# TH_itsy_bitsy_reference_board.net
KiCad netlist of a schematic drawn in EAGLE
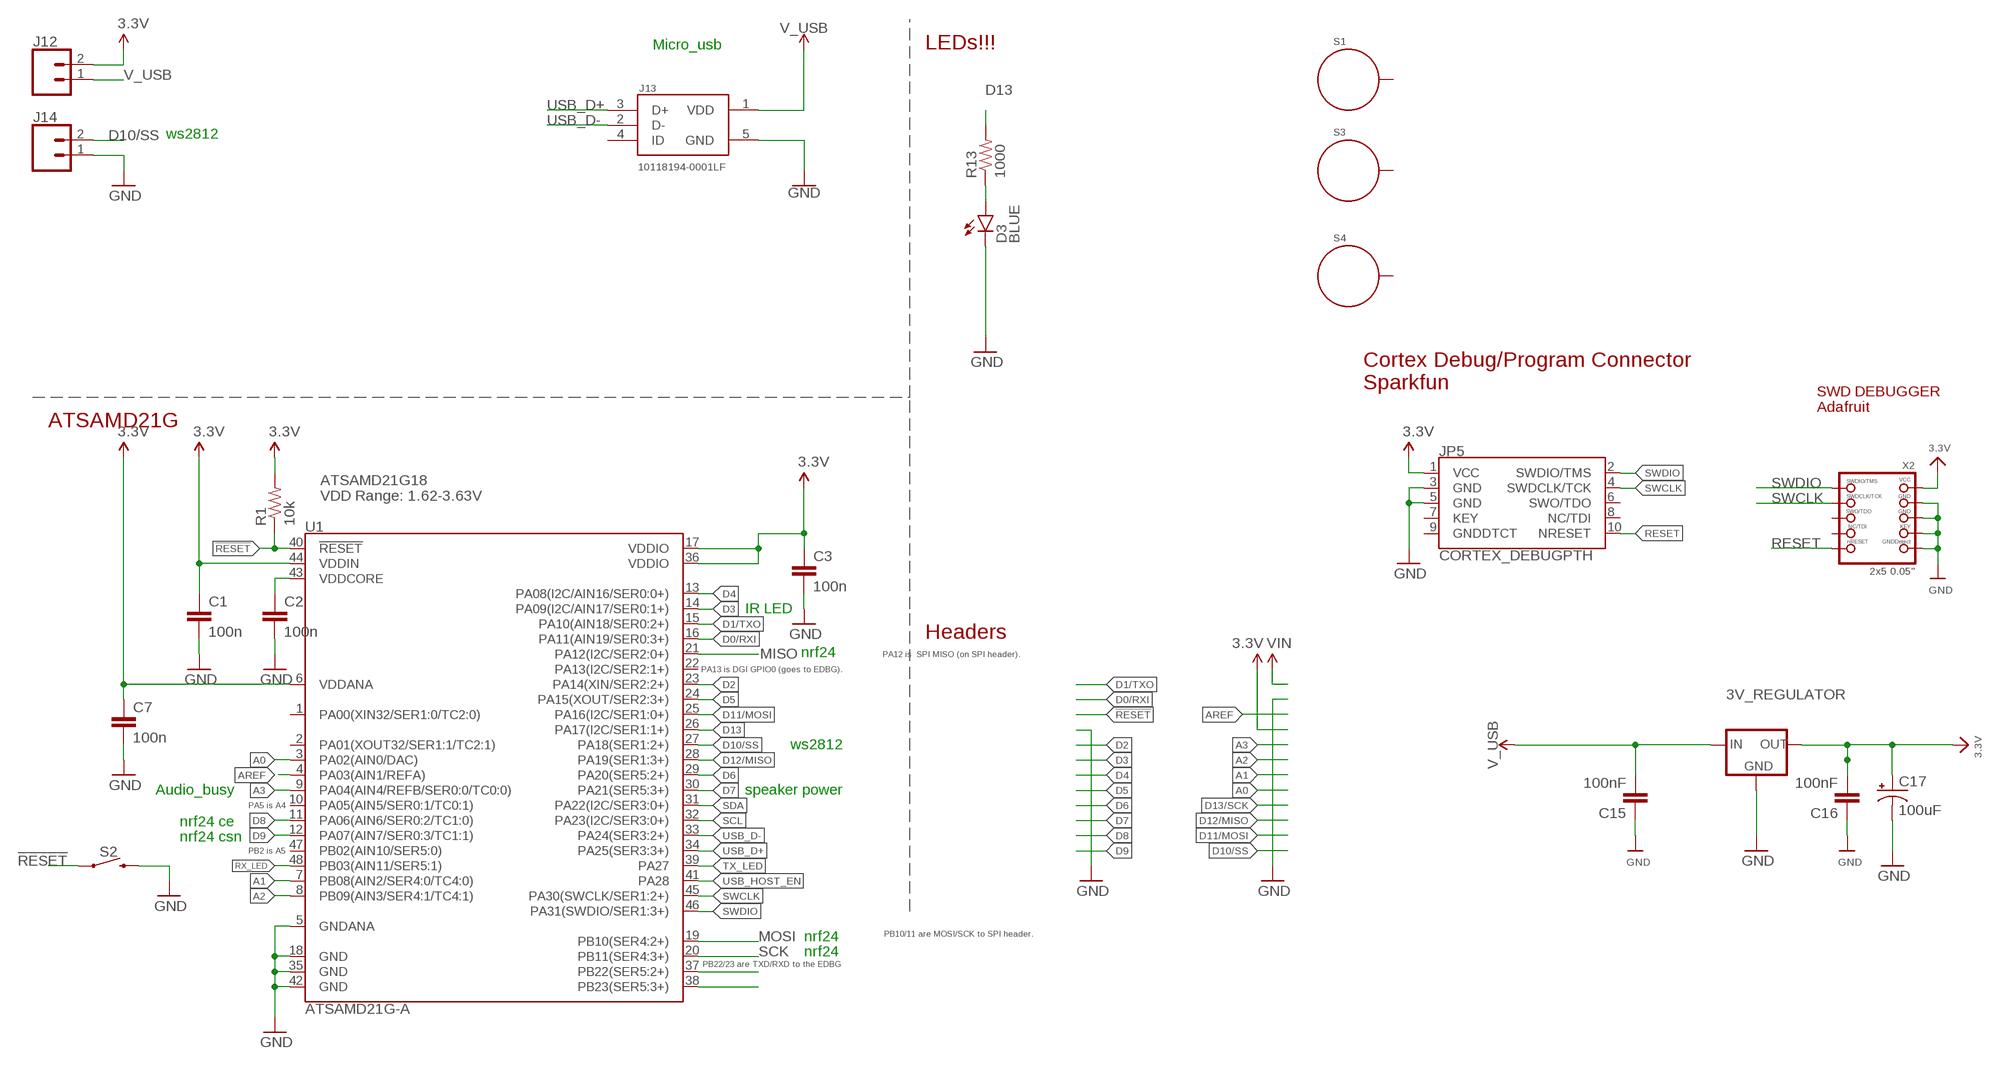
[diagram p0: schematic, sheet 1]

(export (version "E")
  (design (tool "Eeschema 10.0.6"))
  (components
    (comp (ref "3V_REGULATOR")
      (value "LDL1117_5V_REG")
      (footprint "eagle-import:SOT223")
      (libsource (lib "eagle-import") (part "LDL1117_5V_REG"))
    )
    (comp (ref "C1")
      (value "100n")
      (footprint "eagle-import:0805")
      (libsource (lib "eagle-import") (part "CAP0805"))
    )
    (comp (ref "C2")
      (value "100n")
      (footprint "eagle-import:0805")
      (libsource (lib "eagle-import") (part "CAP0805"))
    )
    (comp (ref "C3")
      (value "100n")
      (footprint "eagle-import:0805")
      (libsource (lib "eagle-import") (part "CAP0805"))
    )
    (comp (ref "C7")
      (value "100n")
      (footprint "eagle-import:0805")
      (libsource (lib "eagle-import") (part "CAP0805"))
    )
    (comp (ref "C15")
      (value "100nF")
      (footprint "eagle-import:0805")
      (libsource (lib "eagle-import") (part "10UF-0805-10V-10%"))
    )
    (comp (ref "C16")
      (value "100nF")
      (footprint "eagle-import:0805")
      (libsource (lib "eagle-import") (part "10UF-0805-10V-10%"))
    )
    (comp (ref "C17")
      (value "100uF")
      (footprint "eagle-import:CPOL-RADIAL-2.5MM-6.5MM")
      (libsource (lib "eagle-import") (part "100UF-POLAR-RADIAL-2.5MM-25V-20%"))
    )
    (comp (ref "D3")
      (value "BLUE")
      (footprint "eagle-import:LED-1206")
      (libsource (lib "eagle-import") (part "LED-BLUE1206"))
    )
    (comp (ref "J12")
      (value "CONN_025MM")
      (footprint "eagle-import:SCREWTERMINAL-5MM-2")
      (libsource (lib "eagle-import") (part "CONN_025MM"))
    )
    (comp (ref "J13")
      (value "10118194-0001LF")
      (footprint "eagle-import:FRAMATOME_10118194-0001LF")
      (fields (field (name "MF") "Amphenol ICC"))
      (libsource (lib "eagle-import") (part "10118194-0001LF"))
    )
    (comp (ref "J14")
      (value "CONN_025MM")
      (footprint "eagle-import:SCREWTERMINAL-5MM-2")
      (libsource (lib "eagle-import") (part "CONN_025MM"))
    )
    (comp (ref "JP5")
      (value "CORTEX_DEBUGPTH")
      (footprint "eagle-import:2X5-PTH-1.27MM")
      (libsource (lib "eagle-import") (part "CORTEX_DEBUGPTH"))
    )
    (comp (ref "R1")
      (value "10k")
      (footprint "eagle-import:0805")
      (libsource (lib "eagle-import") (part "RESISTOR0805-RES"))
    )
    (comp (ref "R13")
      (value "1000")
      (footprint "eagle-import:0805")
      (libsource (lib "eagle-import") (part "SparkFun-Passives_RESISTOR0805-RES"))
    )
    (comp (ref "S1")
      (value "STANDOFF_ELECTRICAL144")
      (footprint "eagle-import:STANDOFF_ELECTRICAL_144MILL_NORMAL_SCREW")
      (libsource (lib "eagle-import") (part "STANDOFF_ELECTRICAL144"))
    )
    (comp (ref "S2")
      (value "MOMENTARY-SWITCH-SPST-PTH-6.0MM-KIT")
      (footprint "eagle-import:TACTILE_SWITCH_PTH_6.0MM_KIT")
      (libsource (lib "eagle-import") (part "MOMENTARY-SWITCH-SPST-PTH-6.0MM-KIT"))
    )
    (comp (ref "S3")
      (value "STANDOFF_ELECTRICAL144")
      (footprint "eagle-import:STANDOFF_ELECTRICAL_144MILL_NORMAL_SCREW")
      (libsource (lib "eagle-import") (part "STANDOFF_ELECTRICAL144"))
    )
    (comp (ref "S4")
      (value "STANDOFF_ELECTRICAL144")
      (footprint "eagle-import:STANDOFF_ELECTRICAL_144MILL_NORMAL_SCREW")
      (libsource (lib "eagle-import") (part "STANDOFF_ELECTRICAL144"))
    )
    (comp (ref "U1")
      (value "ATSAMD21G-A")
      (footprint "eagle-import:TQFP-48")
      (libsource (lib "eagle-import") (part "ATSAMD21G-A"))
    )
    (comp (ref "X2")
      (value "2x5 0.05\"")
      (footprint "eagle-import:2X05_1.27MM_BOX_POSTS")
      (libsource (lib "eagle-import") (part "JTAG-CORTEXBOXPOSTS"))
    )
  )
  (nets
    (net (code "1") (name "/MISO") (class "Default")
      (node (ref "U1") (pin "21") (pinfunction "PA12(I2C/SER2:0+)_21") (pintype "bidirectional"))
    )
    (net (code "2") (name "/MOSI") (class "Default")
      (node (ref "U1") (pin "19") (pinfunction "PB10(SER4:2+)_19") (pintype "bidirectional"))
    )
    (net (code "3") (name "/SCK") (class "Default")
      (node (ref "U1") (pin "20") (pinfunction "PB11(SER4:3+)_20") (pintype "bidirectional"))
    )
    (net (code "4") (name "/~{RESET}") (class "Default")
      (node (ref "R1") (pin "1") (pinfunction "1_1") (pintype "passive"))
      (node (ref "S2") (pin "1") (pinfunction "1_1") (pintype "passive"))
      (node (ref "U1") (pin "40") (pinfunction "~{RESET}_40") (pintype "bidirectional"))
    )
    (net (code "5") (name "3.3V") (class "Default")
      (node (ref "3V_REGULATOR") (pin "2") (pinfunction "OUT_2") (pintype "passive"))
      (node (ref "3V_REGULATOR") (pin "4") (pinfunction "OUT_4") (pintype "passive"))
      (node (ref "C1") (pin "1") (pinfunction "1_1") (pintype "passive"))
      (node (ref "C16") (pin "2") (pinfunction "2_2") (pintype "passive"))
      (node (ref "C17") (pin "1") (pinfunction "+_1") (pintype "passive"))
      (node (ref "C3") (pin "1") (pinfunction "1_1") (pintype "passive"))
      (node (ref "C7") (pin "1") (pinfunction "1_1") (pintype "passive"))
      (node (ref "J12") (pin "2") (pinfunction "2_2") (pintype "passive"))
      (node (ref "JP5") (pin "1") (pinfunction "VCC_1") (pintype "bidirectional"))
      (node (ref "R1") (pin "2") (pinfunction "2_2") (pintype "passive"))
      (node (ref "U1") (pin "17") (pinfunction "VDDIO_17") (pintype "bidirectional"))
      (node (ref "U1") (pin "36") (pinfunction "VDDIO_36") (pintype "bidirectional"))
      (node (ref "U1") (pin "44") (pinfunction "VDDIN_44") (pintype "bidirectional"))
      (node (ref "U1") (pin "6") (pinfunction "VDDANA_6") (pintype "bidirectional"))
      (node (ref "X2") (pin "1") (pinfunction "VCC_1") (pintype "power_in"))
    )
    (net (code "6") (name "A0") (class "Default")
      (node (ref "U1") (pin "3") (pinfunction "PA02(AIN0/DAC)_3") (pintype "bidirectional"))
    )
    (net (code "7") (name "A1") (class "Default")
      (node (ref "U1") (pin "7") (pinfunction "PB08(AIN2/SER4:0/TC4:0)_7") (pintype "bidirectional"))
    )
    (net (code "8") (name "A2") (class "Default")
      (node (ref "U1") (pin "8") (pinfunction "PB09(AIN3/SER4:1/TC4:1)_8") (pintype "bidirectional"))
    )
    (net (code "9") (name "A3") (class "Default")
      (node (ref "U1") (pin "9") (pinfunction "PA04(AIN4/REFB/SER0:0/TC0:0)_9") (pintype "bidirectional"))
    )
    (net (code "10") (name "AREF") (class "Default")
      (node (ref "U1") (pin "4") (pinfunction "PA03(AIN1/REFA)_4") (pintype "bidirectional"))
    )
    (net (code "11") (name "D0{slash}RXI") (class "Default")
      (node (ref "U1") (pin "16") (pinfunction "PA11(AIN19/SER0:3+)_16") (pintype "bidirectional"))
    )
    (net (code "12") (name "D1{slash}TXO") (class "Default")
      (node (ref "U1") (pin "15") (pinfunction "PA10(AIN18/SER0:2+)_15") (pintype "bidirectional"))
    )
    (net (code "13") (name "D2") (class "Default")
      (node (ref "U1") (pin "23") (pinfunction "PA14(XIN/SER2:2+)_23") (pintype "bidirectional"))
    )
    (net (code "14") (name "D3") (class "Default")
      (node (ref "U1") (pin "14") (pinfunction "PA09(I2C/AIN17/SER0:1+)_14") (pintype "bidirectional"))
    )
    (net (code "15") (name "D4") (class "Default")
      (node (ref "U1") (pin "13") (pinfunction "PA08(I2C/AIN16/SER0:0+)_13") (pintype "bidirectional"))
    )
    (net (code "16") (name "D5") (class "Default")
      (node (ref "U1") (pin "24") (pinfunction "PA15(XOUT/SER2:3+)_24") (pintype "bidirectional"))
    )
    (net (code "17") (name "D6") (class "Default")
      (node (ref "U1") (pin "29") (pinfunction "PA20(SER5:2+)_29") (pintype "bidirectional"))
    )
    (net (code "18") (name "D7") (class "Default")
      (node (ref "U1") (pin "30") (pinfunction "PA21(SER5:3+)_30") (pintype "bidirectional"))
    )
    (net (code "19") (name "D8") (class "Default")
      (node (ref "U1") (pin "11") (pinfunction "PA06(AIN6/SER0:2/TC1:0)_11") (pintype "bidirectional"))
    )
    (net (code "20") (name "D9") (class "Default")
      (node (ref "U1") (pin "12") (pinfunction "PA07(AIN7/SER0:3/TC1:1)_12") (pintype "bidirectional"))
    )
    (net (code "21") (name "D10{slash}SS") (class "Default")
      (node (ref "J14") (pin "2") (pinfunction "2_2") (pintype "passive"))
      (node (ref "U1") (pin "27") (pinfunction "PA18(SER1:2+)_27") (pintype "bidirectional"))
    )
    (net (code "22") (name "D11{slash}MOSI") (class "Default")
      (node (ref "U1") (pin "25") (pinfunction "PA16(I2C/SER1:0+)_25") (pintype "bidirectional"))
    )
    (net (code "23") (name "D12{slash}MISO") (class "Default")
      (node (ref "U1") (pin "28") (pinfunction "PA19(SER1:3+)_28") (pintype "bidirectional"))
    )
    (net (code "24") (name "D13") (class "Default")
      (node (ref "R13") (pin "2") (pinfunction "2_2") (pintype "passive"))
      (node (ref "U1") (pin "26") (pinfunction "PA17(I2C/SER1:1+)_26") (pintype "bidirectional"))
    )
    (net (code "26") (name "GND") (class "Default")
      (node (ref "3V_REGULATOR") (pin "1") (pinfunction "GND_1") (pintype "input"))
      (node (ref "C1") (pin "2") (pinfunction "2_2") (pintype "passive"))
      (node (ref "C15") (pin "1") (pinfunction "1_1") (pintype "passive"))
      (node (ref "C16") (pin "1") (pinfunction "1_1") (pintype "passive"))
      (node (ref "C17") (pin "2") (pinfunction "-_2") (pintype "passive"))
      (node (ref "C2") (pin "2") (pinfunction "2_2") (pintype "passive"))
      (node (ref "C3") (pin "2") (pinfunction "2_2") (pintype "passive"))
      (node (ref "C7") (pin "2") (pinfunction "2_2") (pintype "passive"))
      (node (ref "D3") (pin "C") (pinfunction "C_C") (pintype "passive"))
      (node (ref "J13") (pin "5") (pinfunction "GND_5") (pintype "power_in"))
      (node (ref "J14") (pin "1") (pinfunction "1_1") (pintype "passive"))
      (node (ref "JP5") (pin "3") (pinfunction "GND_3") (pintype "bidirectional"))
      (node (ref "JP5") (pin "5") (pinfunction "GND_5") (pintype "bidirectional"))
      (node (ref "S2") (pin "3") (pinfunction "2_3") (pintype "passive"))
      (node (ref "U1") (pin "18") (pinfunction "GND_18") (pintype "bidirectional"))
      (node (ref "U1") (pin "35") (pinfunction "GND_35") (pintype "bidirectional"))
      (node (ref "U1") (pin "42") (pinfunction "GND_42") (pintype "bidirectional"))
      (node (ref "U1") (pin "5") (pinfunction "GNDANA_5") (pintype "bidirectional"))
      (node (ref "X2") (pin "3") (pinfunction "GND_3") (pintype "power_in"))
      (node (ref "X2") (pin "5") (pinfunction "GND_5") (pintype "power_in"))
      (node (ref "X2") (pin "7") (pinfunction "KEY_7") (pintype "bidirectional"))
      (node (ref "X2") (pin "9") (pinfunction "GNDDETECT_9") (pintype "bidirectional"))
    )
    (net (code "27") (name "Net-(D3-PadA)") (class "Default")
      (node (ref "D3") (pin "A") (pinfunction "A_A") (pintype "passive"))
      (node (ref "R13") (pin "1") (pinfunction "1_1") (pintype "passive"))
    )
    (net (code "28") (name "Net-(U1-VDDCORE)") (class "Default")
      (node (ref "C2") (pin "1") (pinfunction "1_1") (pintype "passive"))
      (node (ref "U1") (pin "43") (pinfunction "VDDCORE_43") (pintype "bidirectional"))
    )
    (net (code "29") (name "RESET") (class "Default")
      (node (ref "JP5") (pin "10") (pinfunction "NRESET_10") (pintype "bidirectional"))
      (node (ref "X2") (pin "10") (pinfunction "NRESET_10") (pintype "bidirectional"))
    )
    (net (code "30") (name "RX_LED") (class "Default")
      (node (ref "U1") (pin "48") (pinfunction "PB03(AIN11/SER5:1)_48") (pintype "bidirectional"))
    )
    (net (code "31") (name "SCL") (class "Default")
      (node (ref "U1") (pin "32") (pinfunction "PA23(I2C/SER3:0+)_32") (pintype "bidirectional"))
    )
    (net (code "32") (name "SDA") (class "Default")
      (node (ref "U1") (pin "31") (pinfunction "PA22(I2C/SER3:0+)_31") (pintype "bidirectional"))
    )
    (net (code "33") (name "SWCLK") (class "Default")
      (node (ref "JP5") (pin "4") (pinfunction "SWDCLK/TCK_4") (pintype "bidirectional"))
      (node (ref "U1") (pin "45") (pinfunction "PA30(SWCLK/SER1:2+)_45") (pintype "bidirectional"))
      (node (ref "X2") (pin "4") (pinfunction "SWDCLK_4") (pintype "bidirectional"))
    )
    (net (code "34") (name "SWDIO") (class "Default")
      (node (ref "JP5") (pin "2") (pinfunction "SWDIO/TMS_2") (pintype "bidirectional"))
      (node (ref "U1") (pin "46") (pinfunction "PA31(SWDIO/SER1:3+)_46") (pintype "bidirectional"))
      (node (ref "X2") (pin "2") (pinfunction "SWDIO_2") (pintype "bidirectional"))
    )
    (net (code "35") (name "TX_LED") (class "Default")
      (node (ref "U1") (pin "39") (pinfunction "PA27_39") (pintype "bidirectional"))
    )
    (net (code "36") (name "USB_D+") (class "Default")
      (node (ref "J13") (pin "3") (pinfunction "D+_3") (pintype "bidirectional"))
      (node (ref "U1") (pin "34") (pinfunction "PA25(SER3:3+)_34") (pintype "bidirectional"))
    )
    (net (code "37") (name "USB_D-") (class "Default")
      (node (ref "J13") (pin "2") (pinfunction "D-_2") (pintype "bidirectional"))
      (node (ref "U1") (pin "33") (pinfunction "PA24(SER3:2+)_33") (pintype "bidirectional"))
    )
    (net (code "38") (name "USB_HOST_EN") (class "Default")
      (node (ref "U1") (pin "41") (pinfunction "PA28_41") (pintype "bidirectional"))
    )
    (net (code "40") (name "V_USB") (class "Default")
      (node (ref "3V_REGULATOR") (pin "3") (pinfunction "IN_3") (pintype "input"))
      (node (ref "C15") (pin "2") (pinfunction "2_2") (pintype "passive"))
      (node (ref "J12") (pin "1") (pinfunction "1_1") (pintype "passive"))
      (node (ref "J13") (pin "1") (pinfunction "VDD_1") (pintype "power_in"))
    )
    (net (code "41") (name "unconnected-(J13-ID-Pad4)") (class "Default")
      (node (ref "J13") (pin "4") (pinfunction "ID_4") (pintype "passive"))
    )
    (net (code "42") (name "unconnected-(JP5-GNDDTCT-Pad9)") (class "Default")
      (node (ref "JP5") (pin "9") (pinfunction "GNDDTCT_9") (pintype "bidirectional"))
    )
    (net (code "43") (name "unconnected-(JP5-KEY-Pad7)") (class "Default")
      (node (ref "JP5") (pin "7") (pinfunction "KEY_7") (pintype "bidirectional"))
    )
    (net (code "44") (name "unconnected-(JP5-NC{slash}TDI-Pad8)") (class "Default")
      (node (ref "JP5") (pin "8") (pinfunction "NC/TDI_8") (pintype "bidirectional"))
    )
    (net (code "45") (name "unconnected-(JP5-SWO{slash}TDO-Pad6)") (class "Default")
      (node (ref "JP5") (pin "6") (pinfunction "SWO/TDO_6") (pintype "bidirectional"))
    )
    (net (code "46") (name "unconnected-(S1-P$1-PadP1)") (class "Default")
      (node (ref "S1") (pin "P1") (pinfunction "P$1_P1") (pintype "bidirectional"))
    )
    (net (code "47") (name "unconnected-(S3-P$1-PadP1)") (class "Default")
      (node (ref "S3") (pin "P1") (pinfunction "P$1_P1") (pintype "bidirectional"))
    )
    (net (code "48") (name "unconnected-(S4-P$1-PadP1)") (class "Default")
      (node (ref "S4") (pin "P1") (pinfunction "P$1_P1") (pintype "bidirectional"))
    )
    (net (code "49") (name "unconnected-(U1-PA00(XIN32{slash}SER1:0{slash}TC2:0)-Pad1)") (class "Default")
      (node (ref "U1") (pin "1") (pinfunction "PA00(XIN32/SER1:0/TC2:0)_1") (pintype "bidirectional"))
    )
    (net (code "50") (name "unconnected-(U1-PA01(XOUT32{slash}SER1:1{slash}TC2:1)-Pad2)") (class "Default")
      (node (ref "U1") (pin "2") (pinfunction "PA01(XOUT32/SER1:1/TC2:1)_2") (pintype "bidirectional"))
    )
    (net (code "51") (name "unconnected-(U1-PA05(AIN5{slash}SER0:1{slash}TC0:1)-Pad10)") (class "Default")
      (node (ref "U1") (pin "10") (pinfunction "PA05(AIN5/SER0:1/TC0:1)_10") (pintype "bidirectional"))
    )
    (net (code "52") (name "unconnected-(U1-PA13(I2C{slash}SER2:1+)-Pad22)") (class "Default")
      (node (ref "U1") (pin "22") (pinfunction "PA13(I2C/SER2:1+)_22") (pintype "bidirectional"))
    )
    (net (code "53") (name "unconnected-(U1-PB02(AIN10{slash}SER5:0)-Pad47)") (class "Default")
      (node (ref "U1") (pin "47") (pinfunction "PB02(AIN10/SER5:0)_47") (pintype "bidirectional"))
    )
    (net (code "54") (name "unconnected-(U1-PB22(SER5:2+)-Pad37)") (class "Default")
      (node (ref "U1") (pin "37") (pinfunction "PB22(SER5:2+)_37") (pintype "bidirectional"))
    )
    (net (code "55") (name "unconnected-(U1-PB23(SER5:3+)-Pad38)") (class "Default")
      (node (ref "U1") (pin "38") (pinfunction "PB23(SER5:3+)_38") (pintype "bidirectional"))
    )
    (net (code "56") (name "unconnected-(X2-SWO-Pad6)") (class "Default")
      (node (ref "X2") (pin "6") (pinfunction "SWO_6") (pintype "bidirectional"))
    )
    (net (code "57") (name "unconnected-(X2-TDI-Pad8)") (class "Default")
      (node (ref "X2") (pin "8") (pinfunction "TDI_8") (pintype "bidirectional"))
    )
  )
)
